# Power_Managament.net
KiCad netlist of a schematic drawn in Altium Designer
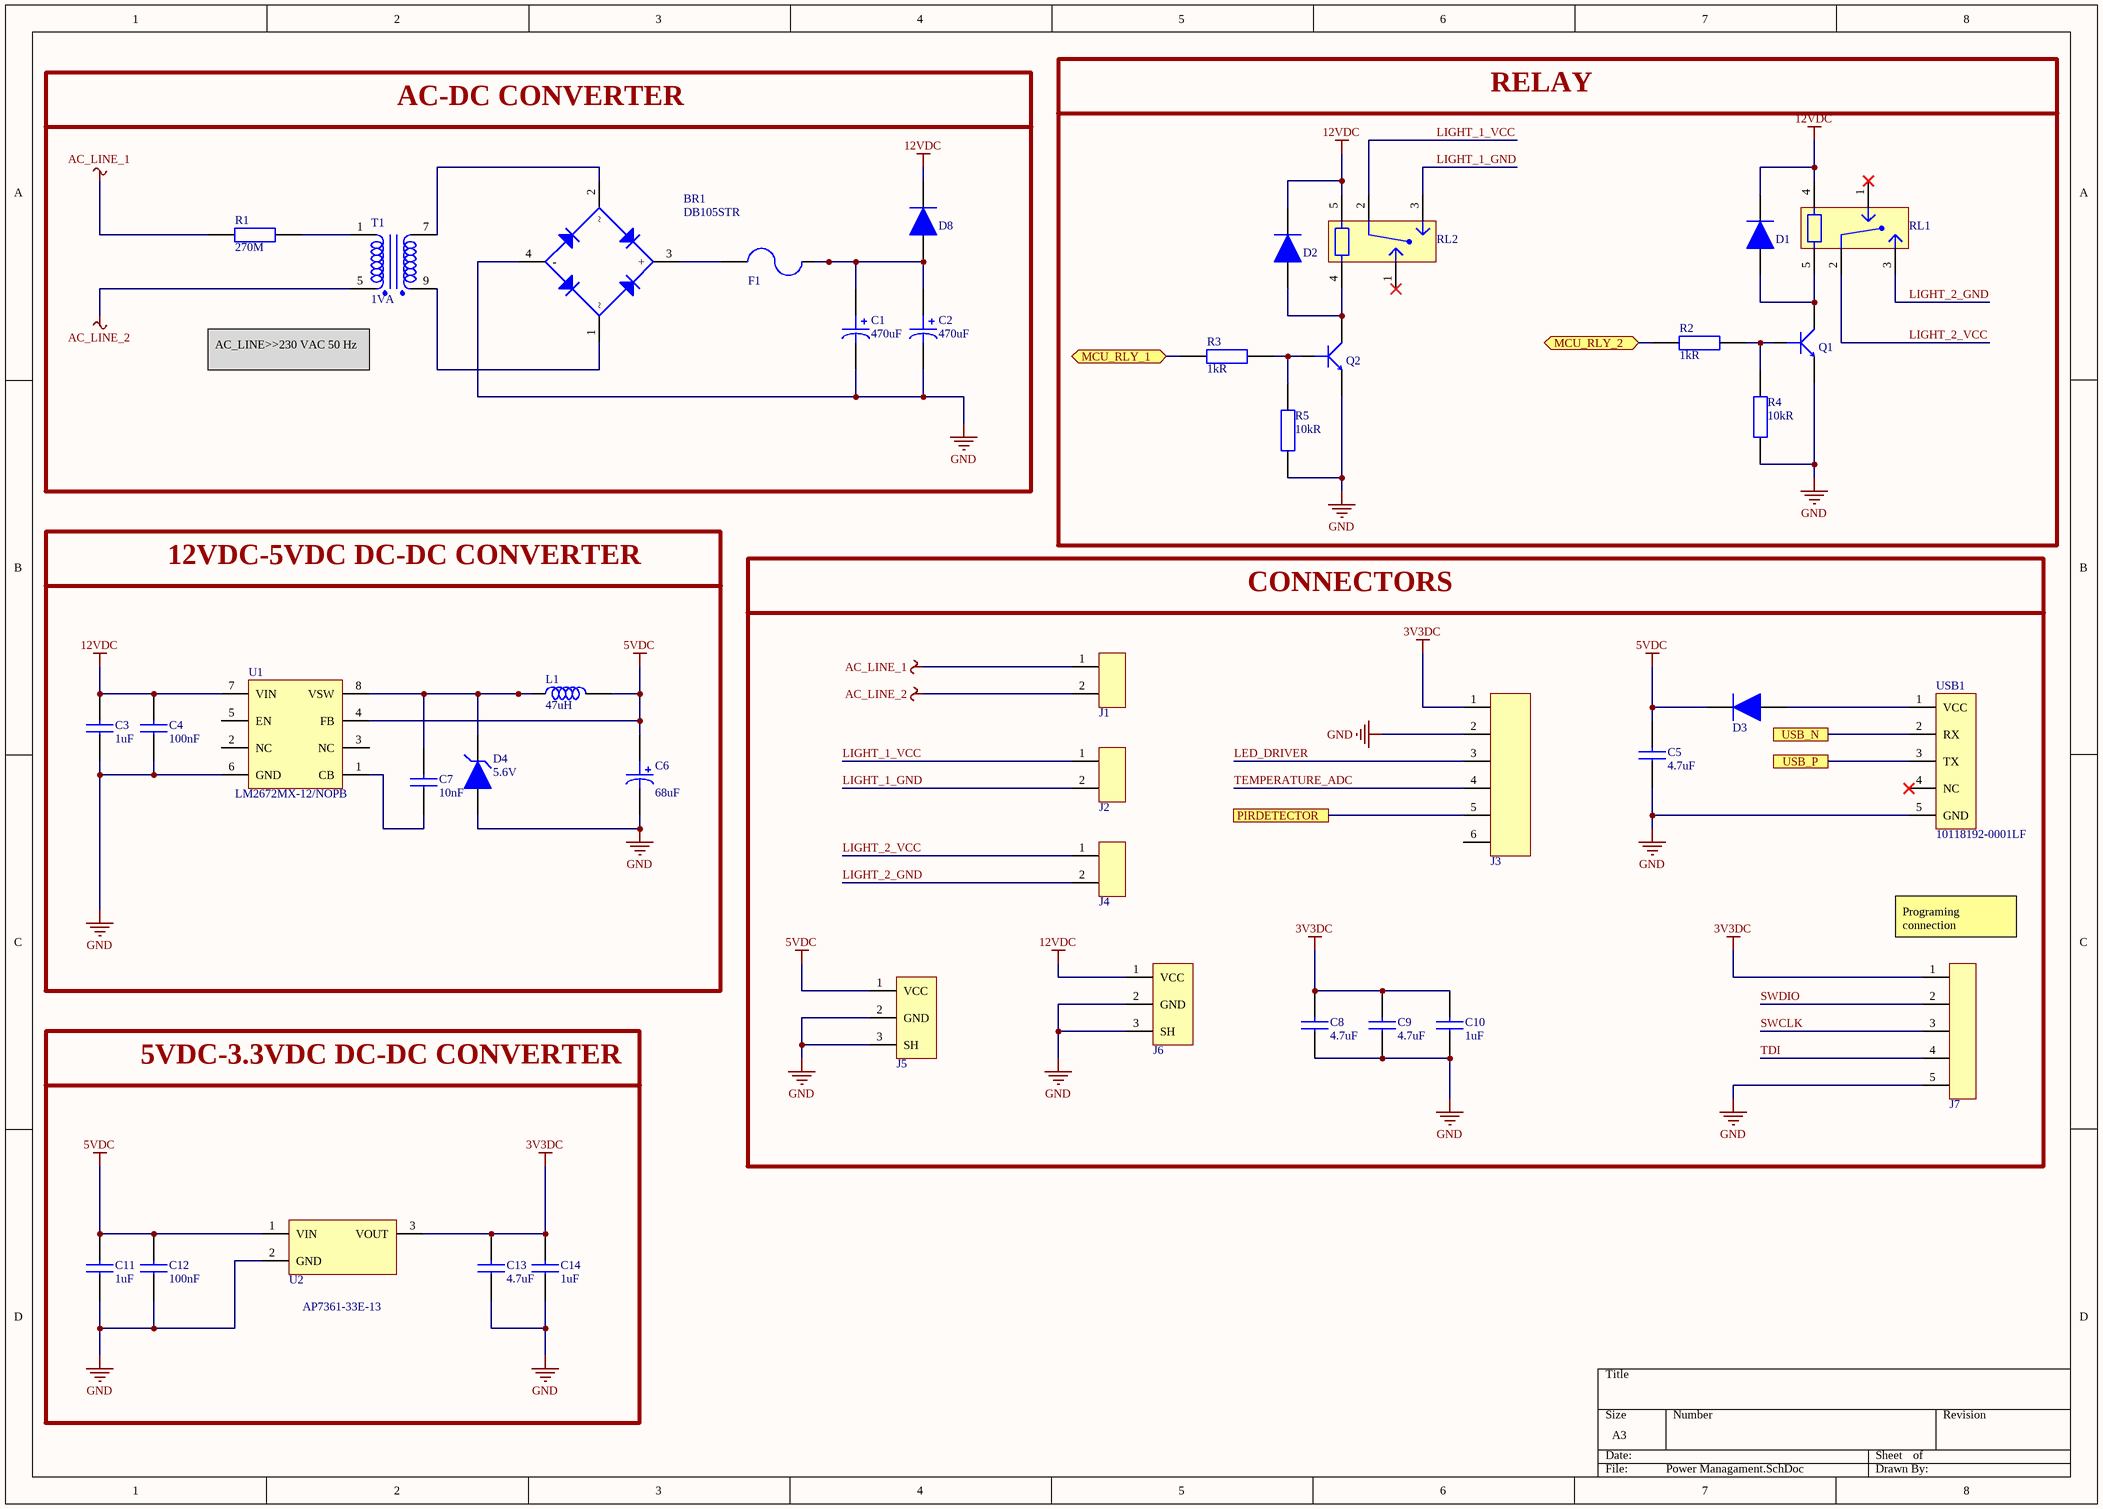
[diagram p0: Power Managament.SchDoc]

(export (version "E")
  (design (tool "Eeschema 10.0.6"))
  (components
    (comp (ref "BR1")
      (value "DB105STR")
      (footprint "DB105STR")
      (fields (field (name "MANUFACTURER") "SMC") (field (name "DESIGNED BY") "TALAT"))
      (libsource (lib "Udemy_Library") (part "DB105STR"))
    )
    (comp (ref "C1")
      (value "ESH477M050AH4AA")
      (footprint "CAP_RADİAL_D10_P5")
      (description "Cap, 470UF, 50V, Alu Elec, Radial")
      (fields
        (field (name "MANUFACTURER") "KEMET")
        (field (name "TOLERANCE") "20%")
        (field (name "CAPACITANCE") "470uF")
        (field (name "DESIGNED BY") "TALAT")
      )
      (libsource (lib "Udemy_Library") (part "ESH477M050AH4AA"))
    )
    (comp (ref "C2")
      (value "ESH477M050AH4AA")
      (footprint "CAP_RADİAL_D10_P5")
      (description "Cap, 470UF, 50V, Alu Elec, Radial")
      (fields
        (field (name "MANUFACTURER") "KEMET")
        (field (name "TOLERANCE") "20%")
        (field (name "CAPACITANCE") "470uF")
        (field (name "DESIGNED BY") "TALAT")
      )
      (libsource (lib "Udemy_Library") (part "ESH477M050AH4AA"))
    )
    (comp (ref "C3")
      (value "CL21B105KBFNNNE")
      (footprint "CAP_0805")
      (description "CAP CER 1uF %10 0805")
      (fields
        (field (name "MANUFACTURER") "Samsung")
        (field (name "TOLERANCE") "10%")
        (field (name "CAPACITANCE") "1uF")
        (field (name "DESIGNED BY") "TALAT")
      )
      (libsource (lib "Udemy_Library") (part "CAP CER 1uF 0805"))
    )
    (comp (ref "C4")
      (value "CL21B104KBCNNNC")
      (footprint "CAP_0805")
      (description "CAP CER 100nF %10 0805")
      (fields
        (field (name "MANUFACTURER") "Samsung")
        (field (name "TOLERANCE") "10%")
        (field (name "CAPACITANCE") "100nF")
        (field (name "DESIGNED BY") "TALAT")
      )
      (libsource (lib "Udemy_Library") (part "CAP CER 100nF 0805"))
    )
    (comp (ref "C5")
      (value "CL21A475KAQNNNE")
      (footprint "CAP_0805")
      (description "CAP CER 4.7uF %10 0805")
      (fields
        (field (name "MANUFACTURER") "Samsung")
        (field (name "TOLERANCE") "10%")
        (field (name "CAPACITANCE") "4.7uF")
        (field (name "DESIGNED BY") "TALAT")
      )
      (libsource (lib "Udemy_Library") (part "CAP CER 4.7uF 0805"))
    )
    (comp (ref "C6")
      (value "EEV686M035A9HAA")
      (footprint "CAP_EEVseries")
      (description "Cap Aluminum Lytic 68uF 35V 20% (6.3 X 7.7mm) SMD 280mA 2000h 105C T/R")
      (fields
        (field (name "MANUFACTURER") "KEMET")
        (field (name "TOLERANCE") "20%")
        (field (name "CAPACITANCE") "68uF")
      )
      (libsource (lib "Udemy_Library") (part "CAP ALU 68uF"))
    )
    (comp (ref "C7")
      (value "0603B103K160CT")
      (footprint "CAP_0603")
      (description "CAP CER 10nF %10 0603")
      (fields
        (field (name "MANUFACTURER") "Walsin Technologies")
        (field (name "TOLERANCE") "10%")
        (field (name "CAPACITANCE") "10nF")
        (field (name "DESIGNED BY") "TALAT")
      )
      (libsource (lib "Udemy_Library") (part "CAP CER 10nF 0603"))
    )
    (comp (ref "C8")
      (value "CL21A475KAQNNNE")
      (footprint "CAP_0805")
      (description "CAP CER 4.7uF %10 0805")
      (fields
        (field (name "MANUFACTURER") "Samsung")
        (field (name "TOLERANCE") "10%")
        (field (name "CAPACITANCE") "4.7uF")
        (field (name "DESIGNED BY") "TALAT")
      )
      (libsource (lib "Udemy_Library") (part "CAP CER 4.7uF 0805"))
    )
    (comp (ref "C9")
      (value "CL21A475KAQNNNE")
      (footprint "CAP_0805")
      (description "CAP CER 4.7uF %10 0805")
      (fields
        (field (name "MANUFACTURER") "Samsung")
        (field (name "TOLERANCE") "10%")
        (field (name "CAPACITANCE") "4.7uF")
        (field (name "DESIGNED BY") "TALAT")
      )
      (libsource (lib "Udemy_Library") (part "CAP CER 4.7uF 0805"))
    )
    (comp (ref "C10")
      (value "CL21B105KBFNNNE")
      (footprint "CAP_0805")
      (description "CAP CER 1uF %10 0805")
      (fields
        (field (name "MANUFACTURER") "Samsung")
        (field (name "TOLERANCE") "10%")
        (field (name "CAPACITANCE") "1uF")
        (field (name "DESIGNED BY") "TALAT")
      )
      (libsource (lib "Udemy_Library") (part "CAP CER 1uF 0805"))
    )
    (comp (ref "C11")
      (value "CL21B105KBFNNNE")
      (footprint "CAP_0805")
      (description "CAP CER 1uF %10 0805")
      (fields
        (field (name "MANUFACTURER") "Samsung")
        (field (name "TOLERANCE") "10%")
        (field (name "CAPACITANCE") "1uF")
        (field (name "DESIGNED BY") "TALAT")
      )
      (libsource (lib "Udemy_Library") (part "CAP CER 1uF 0805"))
    )
    (comp (ref "C12")
      (value "C0603C104K5RACTU")
      (footprint "CAP_0603")
      (description "CAP CER 100nF %10 0603 SMD")
      (fields
        (field (name "MANUFACTURER") "KEMET")
        (field (name "CAPACITANCE") "100nF")
        (field (name "TOLERANCE") "10%")
        (field (name "DESIGNED BY") "TALAT")
      )
      (libsource (lib "Udemy_Library") (part "CAP CER 100nF 0603"))
    )
    (comp (ref "C13")
      (value "CL21A475KAQNNNE")
      (footprint "CAP_0805")
      (description "CAP CER 4.7uF %10 0805")
      (fields
        (field (name "MANUFACTURER") "Samsung")
        (field (name "TOLERANCE") "10%")
        (field (name "CAPACITANCE") "4.7uF")
        (field (name "DESIGNED BY") "TALAT")
      )
      (libsource (lib "Udemy_Library") (part "CAP CER 4.7uF 0805"))
    )
    (comp (ref "C14")
      (value "CL21B105KBFNNNE")
      (footprint "CAP_0805")
      (description "CAP CER 1uF %10 0805")
      (fields
        (field (name "MANUFACTURER") "Samsung")
        (field (name "TOLERANCE") "10%")
        (field (name "CAPACITANCE") "1uF")
        (field (name "DESIGNED BY") "TALAT")
      )
      (libsource (lib "Udemy_Library") (part "CAP CER 1uF 0805"))
    )
    (comp (ref "D1")
      (value "1N4148WS")
      (footprint "SOD323F")
      (description "Diode, Single, 75 V, 150 mA, 1 V, 4 ns")
      (fields
        (field (name "MANUFACTURER") "ON Semiconductor / Fairchild")
        (field (name "DESIGNED BY") "TALAT")
      )
      (libsource (lib "Udemy_Library") (part "1N4148WS"))
    )
    (comp (ref "D2")
      (value "1N4148WS")
      (footprint "SOD323F")
      (description "Diode, Single, 75 V, 150 mA, 1 V, 4 ns")
      (fields
        (field (name "MANUFACTURER") "ON Semiconductor / Fairchild")
        (field (name "DESIGNED BY") "TALAT")
      )
      (libsource (lib "Udemy_Library") (part "1N4148WS"))
    )
    (comp (ref "D3")
      (value "1N4148WS")
      (footprint "SOD323F")
      (description "Diode, Single, 75 V, 150 mA, 1 V, 4 ns")
      (fields
        (field (name "MANUFACTURER") "ON Semiconductor / Fairchild")
        (field (name "DESIGNED BY") "TALAT")
      )
      (libsource (lib "Udemy_Library") (part "1N4148WS"))
    )
    (comp (ref "D4")
      (value "1SMB5919BT3G")
      (footprint "SMB")
      (description "Diode Zener Single 5.6V 5% 3W 2-Pin SMB T/R")
      (fields
        (field (name "MANUFACTURER") "ON Semiconductor")
        (field (name "TOLERANCE") "5%")
        (field (name "WORKING VOLTAGE") "5.6V")
        (field (name "DESIGNED BY") "TALAT")
      )
      (libsource (lib "Udemy_Library") (part "1SMB5919BT3G"))
    )
    (comp (ref "D8")
      (value "1N4148WS")
      (footprint "SOD323F")
      (description "Diode, Single, 75 V, 150 mA, 1 V, 4 ns")
      (fields
        (field (name "MANUFACTURER") "ON Semiconductor / Fairchild")
        (field (name "DESIGNED BY") "TALAT")
      )
      (libsource (lib "Udemy_Library") (part "1N4148WS"))
    )
    (comp (ref "F1")
      (value "3413.0216.22")
      (footprint "3413.0216.2")
      (description "FUSE BRD MNT 1A 32VAC 63VDC 1206")
      (fields (field (name "MANUFACTURER") "Schurter") (field (name "DESIGNED BY") "TALAT"))
      (libsource (lib "Udemy_Library") (part "FUSE 3413.0216.22"))
    )
    (comp (ref "J1")
      (value "TBP01R1-508-02BE")
      (footprint "TBP01R1-508")
      (description "Conn Shrouded Header HDR 2 POS 5.08mm Solder RA Side Entry Thru-Hole Bag")
      (fields (field (name "MANUFACTURER") "CUI") (field (name "DESIGNED BY") "TALAT"))
      (libsource (lib "Udemy_Library") (part "TBP01R1-508-02BE"))
    )
    (comp (ref "J2")
      (value "TBP01R1-508-02BE")
      (footprint "TBP01R1-508")
      (description "Conn Shrouded Header HDR 2 POS 5.08mm Solder RA Side Entry Thru-Hole Bag")
      (fields (field (name "MANUFACTURER") "CUI") (field (name "DESIGNED BY") "TALAT"))
      (libsource (lib "Udemy_Library") (part "TBP01R1-508-02BE"))
    )
    (comp (ref "J3")
      (value "64800611622")
      (footprint "64800611622")
      (description "1.50mm 6PIN Connector")
      (fields (field (name "MANUFACTURER") "Wurth Electronics") (field (name "DESIGNED BY") "TALAT"))
      (libsource (lib "Udemy_Library") (part "64800611622_conn_6pin"))
    )
    (comp (ref "J4")
      (value "TBP01R1-508-02BE")
      (footprint "TBP01R1-508")
      (description "Conn Shrouded Header HDR 2 POS 5.08mm Solder RA Side Entry Thru-Hole Bag")
      (fields (field (name "MANUFACTURER") "CUI") (field (name "DESIGNED BY") "TALAT"))
      (libsource (lib "Udemy_Library") (part "TBP01R1-508-02BE"))
    )
    (comp (ref "J5")
      (value "PJ-037AH-SMT-TR")
      (footprint "JACK")
      (description "DC Power Connectors Power Jacks")
      (fields (field (name "MANUFACTURER") "CUI") (field (name "DESIGNED BY") "TALAT"))
      (libsource (lib "Udemy_Library") (part "PJ-037AH-SMT-TR"))
    )
    (comp (ref "J6")
      (value "PJ-037AH-SMT-TR")
      (footprint "JACK")
      (description "DC Power Connectors Power Jacks")
      (fields (field (name "MANUFACTURER") "CUI") (field (name "DESIGNED BY") "TALAT"))
      (libsource (lib "Udemy_Library") (part "PJ-037AH-SMT-TR"))
    )
    (comp (ref "J7")
      (value "SMH-105-02-L-S")
      (footprint "PINHEADER1X5_RA")
      (description ".100 C.L. HORIZONTAL SMT SOCKET")
      (fields (field (name "MANUFACTURER") "Samtec") (field (name "DESIGNED BY") "TALAT"))
      (libsource (lib "Udemy_Library") (part "SMH-105-02-L-S"))
    )
    (comp (ref "L1")
      (value "78438335470")
      (footprint "IND_1212")
      (description "FIXED IND 47UH 390MA 2.3 OHM SMD")
      (fields
        (field (name "MANUFACTURER") "Wurth Electronics")
        (field (name "TOLERANCE") "30%")
        (field (name "INDUCTANCE") "47uH")
        (field (name "DESIGNED BY") "TALAT")
      )
      (libsource (lib "Udemy_Library") (part "IND 47uH"))
    )
    (comp (ref "Q1")
      (value "MMBT3904-7-F")
      (footprint "SOT-23F")
      (description "Transistor General Purpose BJT NPN 40 Volt 0.2A Automotive 3-Pin SOT-23")
      (fields (field (name "MANUFACTURER") "Diodes Zetex") (field (name "DESIGNED BY") "TALAT"))
      (libsource (lib "Udemy_Library") (part "MMBT3904-7-F"))
    )
    (comp (ref "Q2")
      (value "MMBT3904-7-F")
      (footprint "SOT-23F")
      (description "Transistor General Purpose BJT NPN 40 Volt 0.2A Automotive 3-Pin SOT-23")
      (fields (field (name "MANUFACTURER") "Diodes Zetex") (field (name "DESIGNED BY") "TALAT"))
      (libsource (lib "Udemy_Library") (part "MMBT3904-7-F"))
    )
    (comp (ref "R1")
      (value "5WD27")
      (footprint "RES_AXIAL_W")
      (description "Resistor 5 Watt Cermet Wirewound Flameproof .27 Ohm 5% Axial Lead")
      (fields
        (field (name "MANUFACTURER") "NTE Electronics")
        (field (name "TOLERANCE") "5%")
        (field (name "RESISTANCE") "270M")
        (field (name "DESIGNED BY") "TALAT")
      )
      (libsource (lib "Udemy_Library") (part "5WD27"))
    )
    (comp (ref "R2")
      (value "RC0603FR-0710KL")
      (footprint "RES_0603")
      (description "RES 1K %1 OHM 0603 SMD")
      (fields
        (field (name "MANUFACTURER") "Yageo")
        (field (name "MANUFACTURER PART NUMBER") "RC0603JR-071KL")
        (field (name "RESISTANCE") "1kR")
        (field (name "DESIGNED BY") "TALAT")
      )
      (libsource (lib "Udemy_Library") (part "RES 1K OHM 0603"))
    )
    (comp (ref "R3")
      (value "RC0603FR-0710KL")
      (footprint "RES_0603")
      (description "RES 1K %1 OHM 0603 SMD")
      (fields
        (field (name "MANUFACTURER") "Yageo")
        (field (name "MANUFACTURER PART NUMBER") "RC0603JR-071KL")
        (field (name "RESISTANCE") "1kR")
        (field (name "DESIGNED BY") "TALAT")
      )
      (libsource (lib "Udemy_Library") (part "RES 1K OHM 0603"))
    )
    (comp (ref "R4")
      (value "RC0603FR-0710KL")
      (footprint "RES_0603")
      (description "RES 10K %1 OHM 0603 SMD")
      (fields
        (field (name "MANUFACTURER") "Yageo")
        (field (name "TOLERANCE") "1%")
        (field (name "RESISTANCE") "10kR")
        (field (name "DESIGNED BY") "TALAT")
      )
      (libsource (lib "Udemy_Library") (part "RES 10K OHM 0603"))
    )
    (comp (ref "R5")
      (value "RC0603FR-0710KL")
      (footprint "RES_0603")
      (description "RES 10K %1 OHM 0603 SMD")
      (fields
        (field (name "MANUFACTURER") "Yageo")
        (field (name "TOLERANCE") "1%")
        (field (name "RESISTANCE") "10kR")
        (field (name "DESIGNED BY") "TALAT")
      )
      (libsource (lib "Udemy_Library") (part "RES 10K OHM 0603"))
    )
    (comp (ref "RL1")
      (value "ALQ112")
      (footprint "ALQ112")
      (description "General Purpose Relay SPDT (1 Form C) 12VDC Coil Through Hole")
      (fields (field (name "MANUFACTURER") "Panasonic") (field (name "DESIGNED BY") "TALAT"))
      (libsource (lib "Udemy_Library") (part "ALQ112"))
    )
    (comp (ref "RL2")
      (value "ALQ112")
      (footprint "ALQ112")
      (description "General Purpose Relay SPDT (1 Form C) 12VDC Coil Through Hole")
      (fields (field (name "MANUFACTURER") "Panasonic") (field (name "DESIGNED BY") "TALAT"))
      (libsource (lib "") (part "ALQ112_1"))
    )
    (comp (ref "T1")
      (value "BV302S12010-ZU")
      (footprint "BV302S")
      (description "PWR XFMR LAMINATED 1VA TH")
      (fields
        (field (name "MANUFACTURER") "Zettler Magnetics")
        (field (name "RATED POWER") "1VA")
        (field (name "DESIGNED BY") "TALAT")
      )
      (libsource (lib "Udemy_Library") (part "BV302S12010-ZU"))
    )
    (comp (ref "U1")
      (value "LM2672MX-12/NOPB")
      (footprint "SOIC8")
      (description "IC REG BUCK 12V 1A 8-SOIC")
      (fields (field (name "MANUFACTURER") "TI National Semiconductor") (field (name "DESIGNED BY") "TALAT"))
      (libsource (lib "Udemy_Library") (part "LM2672MX-12/NOPB"))
    )
    (comp (ref "U2")
      (value "AP7361-33E-13")
      (footprint "SOT223")
      (description "LDO Regulator Pos 3.3V 1A 4-Pin(3+Tab) SOT-223 T/R")
      (fields (field (name "MANUFACTURER") "Diodes") (field (name "DESIGNED BY") "TALAT"))
      (libsource (lib "Udemy_Library") (part "AP7361-33E-13"))
    )
    (comp (ref "USB1")
      (value "10118192-0001LF")
      (footprint "MICRO_B_USB")
      (description "CONN RCPT USB2.0 MICRO B SMD R/A")
      (fields (field (name "MANUFACTURER") "Amphenol FCI") (field (name "DESIGNED BY") "TALAT"))
      (libsource (lib "Udemy_Library") (part "Micro B USB Connector"))
    )
  )
  (nets
    (net (code "1") (name "/LED_DRIVER") (class "Default") (node (ref "J3") (pin "3") (pintype "power_in")))
    (net (code "2") (name "/LIGHT_1_GND") (class "Default")
      (node (ref "J2") (pin "2") (pinfunction "2_2") (pintype "power_in"))
      (node (ref "RL2") (pin "3") (pinfunction "3_3") (pintype "passive"))
    )
    (net (code "3") (name "/LIGHT_1_VCC") (class "Default")
      (node (ref "J2") (pin "1") (pinfunction "1_1") (pintype "power_in"))
      (node (ref "RL2") (pin "2") (pinfunction "2_2") (pintype "passive"))
    )
    (net (code "4") (name "/LIGHT_2_GND") (class "Default")
      (node (ref "J4") (pin "2") (pinfunction "2_2") (pintype "power_in"))
      (node (ref "RL1") (pin "3") (pinfunction "3_3") (pintype "passive"))
    )
    (net (code "5") (name "/LIGHT_2_VCC") (class "Default")
      (node (ref "J4") (pin "1") (pinfunction "1_1") (pintype "power_in"))
      (node (ref "RL1") (pin "2") (pinfunction "2_2") (pintype "passive"))
    )
    (net (code "6") (name "/MCU_RLY_1") (class "Default")
      (node (ref "R3") (pin "1") (pinfunction "1_1") (pintype "passive"))
    )
    (net (code "7") (name "/MCU_RLY_2") (class "Default")
      (node (ref "R2") (pin "1") (pinfunction "1_1") (pintype "passive"))
    )
    (net (code "8") (name "/PIRDETECTOR") (class "Default") (node (ref "J3") (pin "5") (pintype "power_in")))
    (net (code "9") (name "/SWCLK") (class "Default")
      (node (ref "J7") (pin "3") (pinfunction "3_3") (pintype "power_in"))
    )
    (net (code "10") (name "/SWDIO") (class "Default")
      (node (ref "J7") (pin "2") (pinfunction "2_2") (pintype "power_in"))
    )
    (net (code "11") (name "/TDI") (class "Default")
      (node (ref "J7") (pin "4") (pinfunction "4_4") (pintype "power_in"))
    )
    (net (code "12") (name "/TEMPERATURE_ADC") (class "Default")
      (node (ref "J3") (pin "4") (pintype "power_in"))
    )
    (net (code "13") (name "/USB_N") (class "Default")
      (node (ref "USB1") (pin "2") (pinfunction "RX_2") (pintype "power_in"))
    )
    (net (code "14") (name "/USB_P") (class "Default")
      (node (ref "USB1") (pin "3") (pinfunction "TX_3") (pintype "power_in"))
    )
    (net (code "15") (name "3V3DC") (class "Default")
      (node (ref "C10") (pin "2") (pinfunction "2_2") (pintype "passive"))
      (node (ref "C13") (pin "2") (pinfunction "2_2") (pintype "passive"))
      (node (ref "C14") (pin "2") (pinfunction "2_2") (pintype "passive"))
      (node (ref "C8") (pin "2") (pinfunction "2_2") (pintype "passive"))
      (node (ref "C9") (pin "2") (pinfunction "2_2") (pintype "passive"))
      (node (ref "J3") (pin "1") (pintype "power_in"))
      (node (ref "J7") (pin "1") (pinfunction "1_1") (pintype "power_in"))
      (node (ref "U2") (pin "3") (pinfunction "VOUT_3") (pintype "passive"))
    )
    (net (code "16") (name "5VDC") (class "Default")
      (node (ref "C11") (pin "2") (pinfunction "2_2") (pintype "passive"))
      (node (ref "C12") (pin "2") (pinfunction "2_2") (pintype "passive"))
      (node (ref "C5") (pin "2") (pinfunction "2_2") (pintype "passive"))
      (node (ref "C6") (pin "1") (pinfunction "1_1") (pintype "passive"))
      (node (ref "D3") (pin "1") (pinfunction "1_1") (pintype "power_in"))
      (node (ref "J5") (pin "1") (pinfunction "VCC_1") (pintype "power_in"))
      (node (ref "L1") (pin "2") (pinfunction "2_2") (pintype "passive"))
      (node (ref "U1") (pin "4") (pinfunction "FB_4") (pintype "passive"))
      (node (ref "U2") (pin "1") (pinfunction "VIN_1") (pintype "passive"))
    )
    (net (code "17") (name "12VDC") (class "Default")
      (node (ref "C3") (pin "2") (pinfunction "2_2") (pintype "passive"))
      (node (ref "C4") (pin "2") (pinfunction "2_2") (pintype "passive"))
      (node (ref "D1") (pin "1") (pinfunction "1_1") (pintype "power_in"))
      (node (ref "D2") (pin "1") (pinfunction "1_1") (pintype "power_in"))
      (node (ref "D8") (pin "1") (pinfunction "1_1") (pintype "power_in"))
      (node (ref "J6") (pin "1") (pinfunction "VCC_1") (pintype "power_in"))
      (node (ref "RL1") (pin "4") (pinfunction "4_4") (pintype "passive"))
      (node (ref "RL2") (pin "5") (pinfunction "5_5") (pintype "passive"))
      (node (ref "U1") (pin "7") (pinfunction "VIN_7") (pintype "passive"))
    )
    (net (code "18") (name "AC_LINE_1") (class "Default")
      (node (ref "J1") (pin "1") (pinfunction "1_1") (pintype "power_in"))
      (node (ref "R1") (pin "1") (pinfunction "1_1") (pintype "passive"))
    )
    (net (code "19") (name "AC_LINE_2") (class "Default")
      (node (ref "J1") (pin "2") (pinfunction "2_2") (pintype "power_in"))
      (node (ref "T1") (pin "5") (pinfunction "5_5") (pintype "passive"))
    )
    (net (code "20") (name "GND") (class "Default")
      (node (ref "BR1") (pin "4") (pinfunction "-_4") (pintype "passive"))
      (node (ref "C1") (pin "2") (pinfunction "2_2") (pintype "passive"))
      (node (ref "C10") (pin "1") (pinfunction "1_1") (pintype "passive"))
      (node (ref "C11") (pin "1") (pinfunction "1_1") (pintype "passive"))
      (node (ref "C12") (pin "1") (pinfunction "1_1") (pintype "passive"))
      (node (ref "C13") (pin "1") (pinfunction "1_1") (pintype "passive"))
      (node (ref "C14") (pin "1") (pinfunction "1_1") (pintype "passive"))
      (node (ref "C2") (pin "2") (pinfunction "2_2") (pintype "passive"))
      (node (ref "C3") (pin "1") (pinfunction "1_1") (pintype "passive"))
      (node (ref "C4") (pin "1") (pinfunction "1_1") (pintype "passive"))
      (node (ref "C5") (pin "1") (pinfunction "1_1") (pintype "passive"))
      (node (ref "C6") (pin "2") (pinfunction "2_2") (pintype "passive"))
      (node (ref "C8") (pin "1") (pinfunction "1_1") (pintype "passive"))
      (node (ref "C9") (pin "1") (pinfunction "1_1") (pintype "passive"))
      (node (ref "D4") (pin "A") (pinfunction "A_A") (pintype "passive"))
      (node (ref "J3") (pin "2") (pintype "power_in"))
      (node (ref "J5") (pin "2") (pinfunction "GND_2") (pintype "power_in"))
      (node (ref "J5") (pin "3") (pinfunction "SH_3") (pintype "power_in"))
      (node (ref "J6") (pin "2") (pinfunction "GND_2") (pintype "power_in"))
      (node (ref "J6") (pin "3") (pinfunction "SH_3") (pintype "power_in"))
      (node (ref "J7") (pin "5") (pinfunction "5_5") (pintype "power_in"))
      (node (ref "Q1") (pin "2") (pinfunction "E_2") (pintype "power_in"))
      (node (ref "Q2") (pin "2") (pinfunction "E_2") (pintype "power_in"))
      (node (ref "R4") (pin "1") (pinfunction "1_1") (pintype "passive"))
      (node (ref "R5") (pin "1") (pinfunction "1_1") (pintype "passive"))
      (node (ref "U1") (pin "6") (pinfunction "GND_6") (pintype "passive"))
      (node (ref "U2") (pin "2") (pinfunction "GND_2") (pintype "passive"))
      (node (ref "USB1") (pin "5") (pinfunction "GND_5") (pintype "power_in"))
    )
    (net (code "21") (name "Net-(BR1-+)") (class "Default")
      (node (ref "BR1") (pin "3") (pinfunction "+_3") (pintype "passive"))
      (node (ref "F1") (pin "1") (pinfunction "1_1") (pintype "passive"))
    )
    (net (code "22") (name "Net-(BR1-~-Pad1)") (class "Default")
      (node (ref "BR1") (pin "1") (pinfunction "~_1") (pintype "passive"))
      (node (ref "T1") (pin "9") (pinfunction "9_9") (pintype "passive"))
    )
    (net (code "23") (name "Net-(BR1-~-Pad2)") (class "Default")
      (node (ref "BR1") (pin "2") (pinfunction "~_2") (pintype "passive"))
      (node (ref "T1") (pin "7") (pinfunction "7_7") (pintype "passive"))
    )
    (net (code "24") (name "Net-(C1-Pad1)") (class "Default")
      (node (ref "C1") (pin "1") (pinfunction "1_1") (pintype "passive"))
      (node (ref "C2") (pin "1") (pinfunction "1_1") (pintype "passive"))
      (node (ref "D8") (pin "2") (pinfunction "2_2") (pintype "power_in"))
      (node (ref "F1") (pin "2") (pinfunction "2_2") (pintype "passive"))
    )
    (net (code "25") (name "Net-(Q1-B)") (class "Default")
      (node (ref "Q1") (pin "1") (pinfunction "B_1") (pintype "power_in"))
      (node (ref "R2") (pin "2") (pinfunction "2_2") (pintype "passive"))
      (node (ref "R4") (pin "2") (pinfunction "2_2") (pintype "passive"))
    )
    (net (code "26") (name "Net-(Q1-C)") (class "Default")
      (node (ref "D1") (pin "2") (pinfunction "2_2") (pintype "power_in"))
      (node (ref "Q1") (pin "3") (pinfunction "C_3") (pintype "power_in"))
      (node (ref "RL1") (pin "5") (pinfunction "5_5") (pintype "passive"))
    )
    (net (code "27") (name "Net-(Q2-B)") (class "Default")
      (node (ref "Q2") (pin "1") (pinfunction "B_1") (pintype "power_in"))
      (node (ref "R3") (pin "2") (pinfunction "2_2") (pintype "passive"))
      (node (ref "R5") (pin "2") (pinfunction "2_2") (pintype "passive"))
    )
    (net (code "28") (name "Net-(Q2-C)") (class "Default")
      (node (ref "D2") (pin "2") (pinfunction "2_2") (pintype "power_in"))
      (node (ref "Q2") (pin "3") (pinfunction "C_3") (pintype "power_in"))
      (node (ref "RL2") (pin "4") (pinfunction "4_4") (pintype "passive"))
    )
    (net (code "29") (name "Net-(R1-Pad2)") (class "Default")
      (node (ref "R1") (pin "2") (pinfunction "2_2") (pintype "passive"))
      (node (ref "T1") (pin "1") (pinfunction "1_1") (pintype "passive"))
    )
    (net (code "30") (name "Net-(U1-CB)") (class "Default")
      (node (ref "C7") (pin "1") (pinfunction "1_1") (pintype "passive"))
      (node (ref "U1") (pin "1") (pinfunction "CB_1") (pintype "passive"))
    )
    (net (code "31") (name "Net-(U1-VSW)") (class "Default")
      (node (ref "C7") (pin "2") (pinfunction "2_2") (pintype "passive"))
      (node (ref "D4") (pin "C") (pinfunction "C_C") (pintype "passive"))
      (node (ref "L1") (pin "1") (pinfunction "1_1") (pintype "passive"))
      (node (ref "U1") (pin "8") (pinfunction "VSW_8") (pintype "passive"))
    )
    (net (code "32") (name "Net-(USB1-VCC)") (class "Default")
      (node (ref "D3") (pin "2") (pinfunction "2_2") (pintype "power_in"))
      (node (ref "USB1") (pin "1") (pinfunction "VCC_1") (pintype "power_in"))
    )
    (net (code "33") (name "unconnected-(J3-Pad6)") (class "Default")
      (node (ref "J3") (pin "6") (pintype "power_in"))
    )
    (net (code "34") (name "unconnected-(RL1-Pad1)") (class "Default")
      (node (ref "RL1") (pin "1") (pinfunction "1_1") (pintype "passive+no_connect"))
    )
    (net (code "35") (name "unconnected-(RL2-Pad1)") (class "Default")
      (node (ref "RL2") (pin "1") (pinfunction "1_1") (pintype "passive+no_connect"))
    )
    (net (code "36") (name "unconnected-(U1-EN-Pad5)") (class "Default")
      (node (ref "U1") (pin "5") (pinfunction "EN_5") (pintype "passive"))
    )
    (net (code "37") (name "unconnected-(U1-NC-Pad2)") (class "Default")
      (node (ref "U1") (pin "2") (pinfunction "NC_2") (pintype "passive"))
    )
    (net (code "38") (name "unconnected-(U1-NC-Pad3)") (class "Default")
      (node (ref "U1") (pin "3") (pinfunction "NC_3") (pintype "passive"))
    )
    (net (code "39") (name "unconnected-(USB1-NC-Pad4)") (class "Default")
      (node (ref "USB1") (pin "4") (pinfunction "NC_4") (pintype "power_in+no_connect"))
    )
  )
)
